# NMEA-v8_3-iso.net
KiCad netlist of a schematic drawn in EAGLE
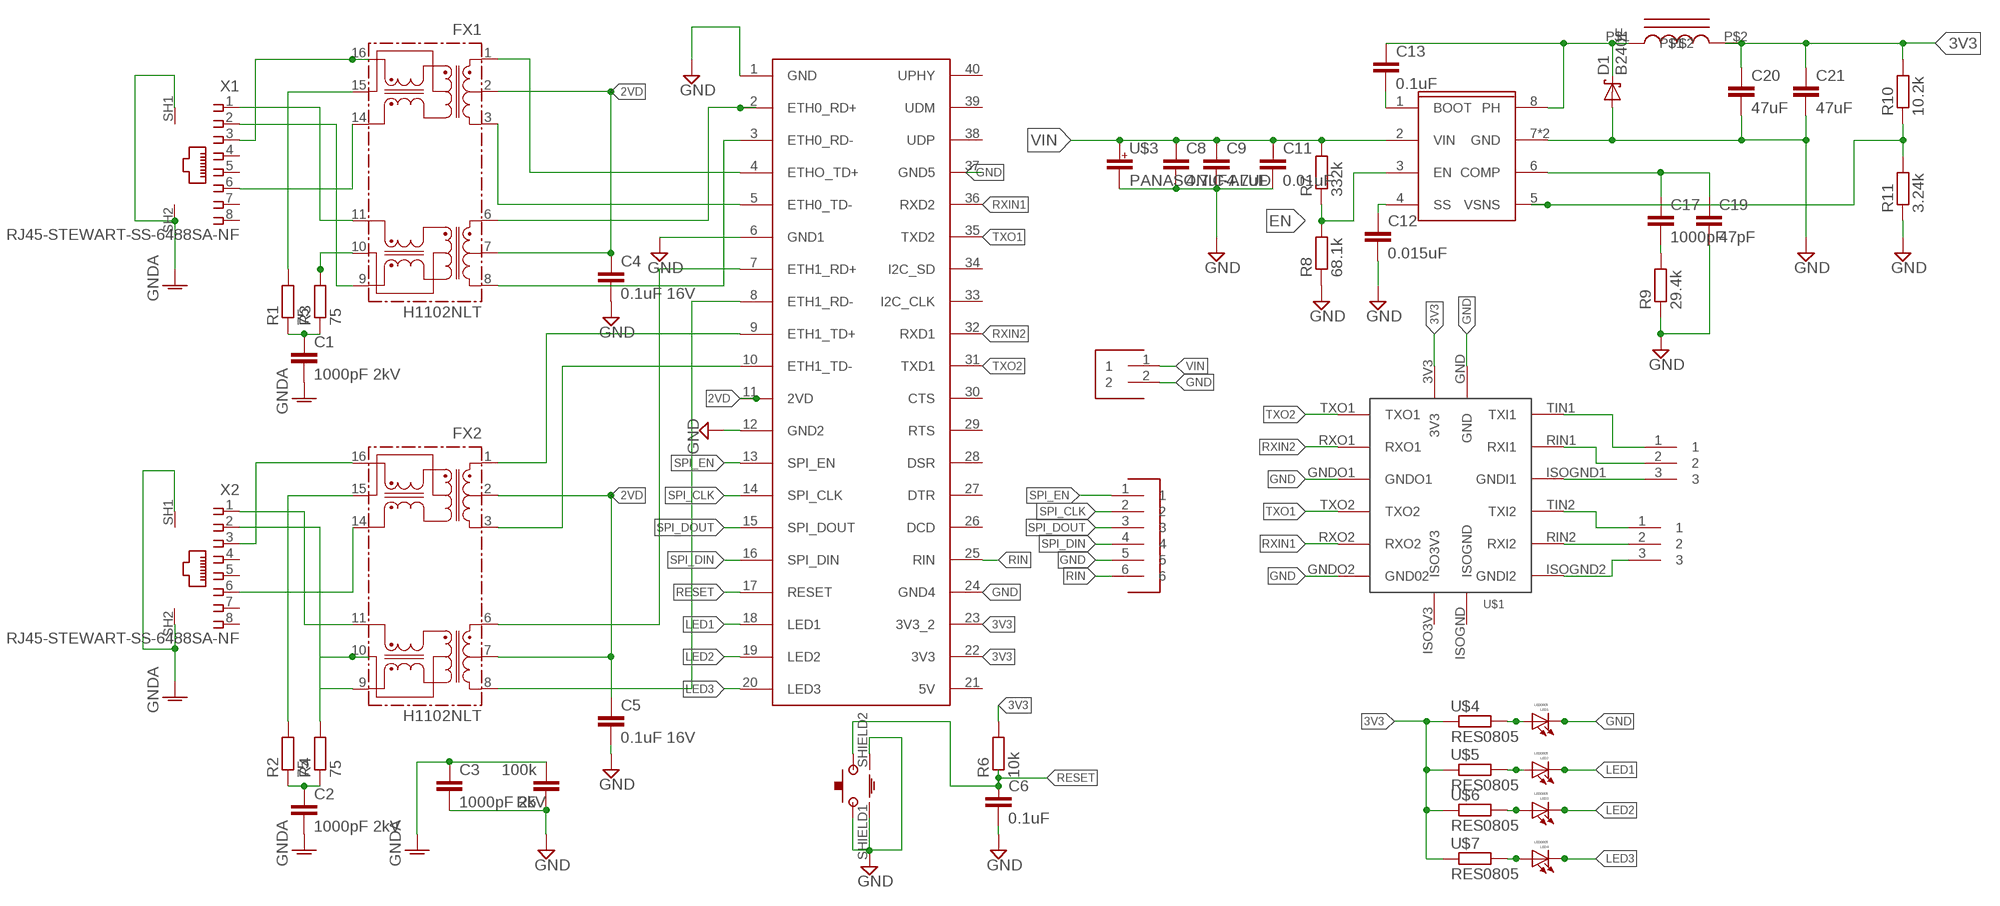
[diagram p0: schematic, sheet 1]

(export (version "E")
  (design (tool "Eeschema 10.0.6"))
  (components
    (comp (ref "C1")
      (value "1000pF 2kV")
      (footprint "eagle-import:1206")
      (libsource (lib "eagle-import") (part "CAP1206"))
    )
    (comp (ref "C2")
      (value "1000pF 2kV")
      (footprint "eagle-import:1206")
      (libsource (lib "eagle-import") (part "CAP1206"))
    )
    (comp (ref "C3")
      (value "1000pF 2kV")
      (footprint "eagle-import:1206")
      (libsource (lib "eagle-import") (part "CAP1206"))
    )
    (comp (ref "C4")
      (value "0.1uF 16V")
      (footprint "eagle-import:0603")
      (libsource (lib "eagle-import") (part "CAP0603"))
    )
    (comp (ref "C5")
      (value "0.1uF 16V")
      (footprint "eagle-import:0603")
      (libsource (lib "eagle-import") (part "CAP0603"))
    )
    (comp (ref "C6")
      (value "0.1uF")
      (footprint "eagle-import:0603")
      (libsource (lib "eagle-import") (part "CAP0603"))
    )
    (comp (ref "C8")
      (value "4.7uF")
      (footprint "eagle-import:1210")
      (libsource (lib "eagle-import") (part "CAP1210"))
    )
    (comp (ref "C9")
      (value "4.7uF")
      (footprint "eagle-import:1210")
      (libsource (lib "eagle-import") (part "CAP1210"))
    )
    (comp (ref "C11")
      (value "0.01uF")
      (footprint "eagle-import:0603")
      (libsource (lib "eagle-import") (part "CAP0603"))
    )
    (comp (ref "C12")
      (value "0.015uF")
      (footprint "eagle-import:0603")
      (libsource (lib "eagle-import") (part "CAP0603"))
    )
    (comp (ref "C13")
      (value "0.1uF")
      (footprint "eagle-import:0603")
      (libsource (lib "eagle-import") (part "CAP0603"))
    )
    (comp (ref "C17")
      (value "1000pF")
      (footprint "eagle-import:0603")
      (libsource (lib "eagle-import") (part "CAP0603"))
    )
    (comp (ref "C19")
      (value "47pF")
      (footprint "eagle-import:0603")
      (libsource (lib "eagle-import") (part "CAP0603"))
    )
    (comp (ref "C20")
      (value "47uF")
      (footprint "eagle-import:1206")
      (libsource (lib "eagle-import") (part "CAP1206"))
    )
    (comp (ref "C21")
      (value "47uF")
      (footprint "eagle-import:1206")
      (libsource (lib "eagle-import") (part "CAP1206"))
    )
    (comp (ref "CARAMBOLA")
      (value "CARAMBOLACREAM")
      (footprint "eagle-import:CARAMBOLA-CREAM")
      (libsource (lib "eagle-import") (part "CARAMBOLACREAM"))
    )
    (comp (ref "D1")
      (value "B240F")
      (footprint "eagle-import:SMB")
      (libsource (lib "eagle-import") (part "B240F"))
    )
    (comp (ref "DATA1")
      (value "CON-3CREAM")
      (footprint "eagle-import:CON-3-CREAM")
      (libsource (lib "eagle-import") (part "CON-3CREAM"))
    )
    (comp (ref "DATA2")
      (value "CON-3CREAM")
      (footprint "eagle-import:CON-3-CREAM")
      (libsource (lib "eagle-import") (part "CON-3CREAM"))
    )
    (comp (ref "FX1")
      (value "H1102NLT")
      (footprint "eagle-import:H_HX1XXXNL")
      (libsource (lib "eagle-import") (part "H1102NLT"))
    )
    (comp (ref "FX2")
      (value "H1102NLT")
      (footprint "eagle-import:H_HX1XXXNL")
      (libsource (lib "eagle-import") (part "H1102NLT"))
    )
    (comp (ref "J1")
      (value "CON-5MM-2")
      (footprint "eagle-import:CON--5MM-2")
      (libsource (lib "eagle-import") (part "CON-5MM-2"))
    )
    (comp (ref "L1")
      (value "CLF_TDK_INDUCTORCLF10040")
      (footprint "eagle-import:CLF10040")
      (libsource (lib "eagle-import") (part "CLF_TDK_INDUCTORCLF10040"))
    )
    (comp (ref "LED1")
      (value "LED0805")
      (footprint "eagle-import:L0805")
      (libsource (lib "eagle-import") (part "LED0805"))
    )
    (comp (ref "LED2")
      (value "LED0805")
      (footprint "eagle-import:L0805")
      (libsource (lib "eagle-import") (part "LED0805"))
    )
    (comp (ref "LED3")
      (value "LED0805")
      (footprint "eagle-import:L0805")
      (libsource (lib "eagle-import") (part "LED0805"))
    )
    (comp (ref "LED4")
      (value "LED0805")
      (footprint "eagle-import:L0805")
      (libsource (lib "eagle-import") (part "LED0805"))
    )
    (comp (ref "R1")
      (value "75")
      (footprint "eagle-import:0603")
      (libsource (lib "eagle-import") (part "RES0603"))
    )
    (comp (ref "R2")
      (value "75")
      (footprint "eagle-import:0603")
      (libsource (lib "eagle-import") (part "RES0603"))
    )
    (comp (ref "R3")
      (value "75")
      (footprint "eagle-import:0603")
      (libsource (lib "eagle-import") (part "RES0603"))
    )
    (comp (ref "R4")
      (value "75")
      (footprint "eagle-import:0603")
      (libsource (lib "eagle-import") (part "RES0603"))
    )
    (comp (ref "R5")
      (value "100k")
      (footprint "eagle-import:1206")
      (libsource (lib "eagle-import") (part "CAP1206"))
    )
    (comp (ref "R6")
      (value "10k")
      (footprint "eagle-import:0603")
      (libsource (lib "eagle-import") (part "RES0603"))
    )
    (comp (ref "R7")
      (value "332k")
      (footprint "eagle-import:0603")
      (libsource (lib "eagle-import") (part "RES0603"))
    )
    (comp (ref "R8")
      (value "68.1k")
      (footprint "eagle-import:0603")
      (libsource (lib "eagle-import") (part "RES0603"))
    )
    (comp (ref "R9")
      (value "29.4k")
      (footprint "eagle-import:0603")
      (libsource (lib "eagle-import") (part "RES0603"))
    )
    (comp (ref "R10")
      (value "10.2k")
      (footprint "eagle-import:0603")
      (libsource (lib "eagle-import") (part "RES0603"))
    )
    (comp (ref "R11")
      (value "3.24k")
      (footprint "eagle-import:0603")
      (libsource (lib "eagle-import") (part "RES0603"))
    )
    (comp (ref "U$1")
      (value "ISO-BOARDV1")
      (footprint "eagle-import:ISO-BOARD")
      (libsource (lib "eagle-import") (part "ISO-BOARDV1"))
    )
    (comp (ref "U$2")
      (value "TACTILE-SWITCH-FSMRA1J")
      (footprint "eagle-import:TACTILE-SWITCH-FSMRA1J")
      (libsource (lib "eagle-import") (part "TACTILE-SWITCH-FSMRA1J"))
    )
    (comp (ref "U$3")
      (value "PANASONIC-ALUD")
      (footprint "eagle-import:PANASONIC_D")
      (libsource (lib "eagle-import") (part "PANASONIC-ALUD"))
    )
    (comp (ref "U$4")
      (value "RES0805")
      (footprint "eagle-import:0603")
      (libsource (lib "eagle-import") (part "RES0603"))
    )
    (comp (ref "U$5")
      (value "RES0805")
      (footprint "eagle-import:0603")
      (libsource (lib "eagle-import") (part "RES0603"))
    )
    (comp (ref "U$6")
      (value "RES0805")
      (footprint "eagle-import:0603")
      (libsource (lib "eagle-import") (part "RES0603"))
    )
    (comp (ref "U$7")
      (value "RES0805")
      (footprint "eagle-import:0603")
      (libsource (lib "eagle-import") (part "RES0603"))
    )
    (comp (ref "U$8")
      (value "CON-6")
      (footprint "eagle-import:CON-6")
      (libsource (lib "eagle-import") (part "CON-6"))
    )
    (comp (ref "U8")
      (value "TPS54231")
      (footprint "eagle-import:SOIC-THERMAL")
      (libsource (lib "eagle-import") (part "TPS54231"))
    )
    (comp (ref "X1")
      (value "RJ45-STEWART-SS-6488SA-NF")
      (footprint "eagle-import:RJ45-STEWART-6488")
      (libsource (lib "eagle-import") (part "RJ45-STEWART-SS-6488SA-NF"))
    )
    (comp (ref "X2")
      (value "RJ45-STEWART-SS-6488SA-NF")
      (footprint "eagle-import:RJ45-STEWART-6488")
      (libsource (lib "eagle-import") (part "RJ45-STEWART-SS-6488SA-NF"))
    )
  )
  (nets
    (net (code "1") (name "2VD") (class "Default")
      (node (ref "C4") (pin "1") (pinfunction "1_1") (pintype "passive"))
      (node (ref "C5") (pin "1") (pinfunction "1_1") (pintype "passive"))
      (node (ref "CARAMBOLA") (pin "11") (pinfunction "2VD_11") (pintype "bidirectional"))
      (node (ref "FX1") (pin "2") (pinfunction "2_2") (pintype "passive"))
      (node (ref "FX1") (pin "7") (pinfunction "7_7") (pintype "passive"))
      (node (ref "FX2") (pin "2") (pinfunction "2_2") (pintype "passive"))
      (node (ref "FX2") (pin "7") (pinfunction "7_7") (pintype "passive"))
    )
    (net (code "2") (name "3V3") (class "Default")
      (node (ref "C20") (pin "1") (pinfunction "1_1") (pintype "passive"))
      (node (ref "C21") (pin "1") (pinfunction "1_1") (pintype "passive"))
      (node (ref "CARAMBOLA") (pin "22") (pinfunction "3V3_22") (pintype "bidirectional"))
      (node (ref "CARAMBOLA") (pin "23") (pinfunction "3V3_2_23") (pintype "bidirectional"))
      (node (ref "L1") (pin "P$2") (pinfunction "P$2_P$2") (pintype "bidirectional"))
      (node (ref "R10") (pin "2") (pinfunction "2_2") (pintype "passive"))
      (node (ref "R6") (pin "2") (pinfunction "2_2") (pintype "passive"))
      (node (ref "U$1") (pin "3V3") (pinfunction "3V3_3V3") (pintype "bidirectional"))
      (node (ref "U$4") (pin "1") (pinfunction "1_1") (pintype "passive"))
      (node (ref "U$5") (pin "1") (pinfunction "1_1") (pintype "passive"))
      (node (ref "U$6") (pin "1") (pinfunction "1_1") (pintype "passive"))
      (node (ref "U$7") (pin "1") (pinfunction "1_1") (pintype "passive"))
    )
    (net (code "3") (name "EN") (class "Default")
      (node (ref "R7") (pin "1") (pinfunction "1_1") (pintype "passive"))
      (node (ref "R8") (pin "2") (pinfunction "2_2") (pintype "passive"))
      (node (ref "U8") (pin "3") (pinfunction "EN_3") (pintype "bidirectional"))
    )
    (net (code "4") (name "GND") (class "Default")
      (node (ref "C11") (pin "2") (pinfunction "2_2") (pintype "passive"))
      (node (ref "C12") (pin "2") (pinfunction "2_2") (pintype "passive"))
      (node (ref "C19") (pin "2") (pinfunction "2_2") (pintype "passive"))
      (node (ref "C20") (pin "2") (pinfunction "2_2") (pintype "passive"))
      (node (ref "C21") (pin "2") (pinfunction "2_2") (pintype "passive"))
      (node (ref "C3") (pin "2") (pinfunction "2_2") (pintype "passive"))
      (node (ref "C4") (pin "2") (pinfunction "2_2") (pintype "passive"))
      (node (ref "C5") (pin "2") (pinfunction "2_2") (pintype "passive"))
      (node (ref "C6") (pin "2") (pinfunction "2_2") (pintype "passive"))
      (node (ref "C8") (pin "2") (pinfunction "2_2") (pintype "passive"))
      (node (ref "C9") (pin "2") (pinfunction "2_2") (pintype "passive"))
      (node (ref "CARAMBOLA") (pin "1") (pinfunction "GND_1") (pintype "bidirectional"))
      (node (ref "CARAMBOLA") (pin "12") (pinfunction "GND2_12") (pintype "bidirectional"))
      (node (ref "CARAMBOLA") (pin "24") (pinfunction "GND4_24") (pintype "bidirectional"))
      (node (ref "CARAMBOLA") (pin "37") (pinfunction "GND5_37") (pintype "bidirectional"))
      (node (ref "CARAMBOLA") (pin "6") (pinfunction "GND1_6") (pintype "bidirectional"))
      (node (ref "D1") (pin "A") (pinfunction "A_A") (pintype "passive"))
      (node (ref "J1") (pin "2") (pinfunction "2_2") (pintype "bidirectional"))
      (node (ref "LED1") (pin "C") (pinfunction "C_C") (pintype "passive"))
      (node (ref "R11") (pin "1") (pinfunction "1_1") (pintype "passive"))
      (node (ref "R5") (pin "1") (pinfunction "1_1") (pintype "passive"))
      (node (ref "R8") (pin "1") (pinfunction "1_1") (pintype "passive"))
      (node (ref "R9") (pin "1") (pinfunction "1_1") (pintype "passive"))
      (node (ref "U$1") (pin "GND") (pinfunction "GND_GND") (pintype "bidirectional"))
      (node (ref "U$1") (pin "GNDO1") (pinfunction "GNDO1_GNDO1") (pintype "bidirectional"))
      (node (ref "U$1") (pin "GNDO2") (pinfunction "GND02_GNDO2") (pintype "bidirectional"))
      (node (ref "U$2") (pin "2") (pinfunction "2_2") (pintype "bidirectional"))
      (node (ref "U$2") (pin "SHIELD1") (pinfunction "SHIELD1_SHIELD1") (pintype "bidirectional"))
      (node (ref "U$2") (pin "SHIELD2") (pinfunction "SHIELD2_SHIELD2") (pintype "bidirectional"))
      (node (ref "U$3") (pin "-") (pinfunction "-_-") (pintype "passive"))
      (node (ref "U$8") (pin "5") (pinfunction "5_5") (pintype "bidirectional"))
      (node (ref "U8") (pin "7") (pinfunction "GND_7") (pintype "bidirectional"))
      (node (ref "U8") (pin "P$1") (pinfunction "GND_P$1") (pintype "bidirectional"))
    )
    (net (code "5") (name "GNDA") (class "Default")
      (node (ref "C1") (pin "2") (pinfunction "2_2") (pintype "passive"))
      (node (ref "C2") (pin "2") (pinfunction "2_2") (pintype "passive"))
      (node (ref "C3") (pin "1") (pinfunction "1_1") (pintype "passive"))
      (node (ref "R5") (pin "2") (pinfunction "2_2") (pintype "passive"))
      (node (ref "X1") (pin "SH1") (pinfunction "SH1_SH1") (pintype "bidirectional"))
      (node (ref "X1") (pin "SH2") (pinfunction "SH2_SH2") (pintype "bidirectional"))
      (node (ref "X2") (pin "SH1") (pinfunction "SH1_SH1") (pintype "bidirectional"))
      (node (ref "X2") (pin "SH2") (pinfunction "SH2_SH2") (pintype "bidirectional"))
    )
    (net (code "6") (name "LED1") (class "Default")
      (node (ref "CARAMBOLA") (pin "18") (pinfunction "LED1_18") (pintype "bidirectional"))
      (node (ref "LED2") (pin "C") (pinfunction "C_C") (pintype "passive"))
    )
    (net (code "7") (name "LED2") (class "Default")
      (node (ref "CARAMBOLA") (pin "19") (pinfunction "LED2_19") (pintype "bidirectional"))
      (node (ref "LED3") (pin "C") (pinfunction "C_C") (pintype "passive"))
    )
    (net (code "8") (name "LED3") (class "Default")
      (node (ref "CARAMBOLA") (pin "20") (pinfunction "LED3_20") (pintype "bidirectional"))
      (node (ref "LED4") (pin "C") (pinfunction "C_C") (pintype "passive"))
    )
    (net (code "9") (name "Net-(C1-Pad1)") (class "Default")
      (node (ref "C1") (pin "1") (pinfunction "1_1") (pintype "passive"))
      (node (ref "R1") (pin "1") (pinfunction "1_1") (pintype "passive"))
      (node (ref "R3") (pin "1") (pinfunction "1_1") (pintype "passive"))
    )
    (net (code "10") (name "Net-(C2-Pad1)") (class "Default")
      (node (ref "C2") (pin "1") (pinfunction "1_1") (pintype "passive"))
      (node (ref "R2") (pin "1") (pinfunction "1_1") (pintype "passive"))
      (node (ref "R4") (pin "1") (pinfunction "1_1") (pintype "passive"))
    )
    (net (code "11") (name "Net-(C17-Pad2)") (class "Default")
      (node (ref "C17") (pin "2") (pinfunction "2_2") (pintype "passive"))
      (node (ref "R9") (pin "2") (pinfunction "2_2") (pintype "passive"))
    )
    (net (code "12") (name "Net-(CARAMBOLA-ETH0_RD+)") (class "Default")
      (node (ref "CARAMBOLA") (pin "2") (pinfunction "ETH0_RD+_2") (pintype "bidirectional"))
      (node (ref "FX1") (pin "6") (pinfunction "6_6") (pintype "passive"))
    )
    (net (code "13") (name "Net-(CARAMBOLA-ETH0_RD-)") (class "Default")
      (node (ref "CARAMBOLA") (pin "3") (pinfunction "ETH0_RD-_3") (pintype "bidirectional"))
      (node (ref "FX1") (pin "8") (pinfunction "8_8") (pintype "passive"))
    )
    (net (code "14") (name "Net-(CARAMBOLA-ETH0_TD-)") (class "Default")
      (node (ref "CARAMBOLA") (pin "5") (pinfunction "ETH0_TD-_5") (pintype "bidirectional"))
      (node (ref "FX1") (pin "3") (pinfunction "3_3") (pintype "passive"))
    )
    (net (code "15") (name "Net-(CARAMBOLA-ETH1_RD+)") (class "Default")
      (node (ref "CARAMBOLA") (pin "7") (pinfunction "ETH1_RD+_7") (pintype "bidirectional"))
      (node (ref "FX2") (pin "6") (pinfunction "6_6") (pintype "passive"))
    )
    (net (code "16") (name "Net-(CARAMBOLA-ETH1_RD-)") (class "Default")
      (node (ref "CARAMBOLA") (pin "8") (pinfunction "ETH1_RD-_8") (pintype "bidirectional"))
      (node (ref "FX2") (pin "8") (pinfunction "8_8") (pintype "passive"))
    )
    (net (code "17") (name "Net-(CARAMBOLA-ETH1_TD+)") (class "Default")
      (node (ref "CARAMBOLA") (pin "9") (pinfunction "ETH1_TD+_9") (pintype "bidirectional"))
      (node (ref "FX2") (pin "1") (pinfunction "1_1") (pintype "passive"))
    )
    (net (code "18") (name "Net-(CARAMBOLA-ETH1_TD-)") (class "Default")
      (node (ref "CARAMBOLA") (pin "10") (pinfunction "ETH1_TD-_10") (pintype "bidirectional"))
      (node (ref "FX2") (pin "3") (pinfunction "3_3") (pintype "passive"))
    )
    (net (code "19") (name "Net-(CARAMBOLA-ETHO_TD+)") (class "Default")
      (node (ref "CARAMBOLA") (pin "4") (pinfunction "ETHO_TD+_4") (pintype "bidirectional"))
      (node (ref "FX1") (pin "1") (pinfunction "1_1") (pintype "passive"))
    )
    (net (code "20") (name "Net-(FX1-Pad9)") (class "Default")
      (node (ref "FX1") (pin "9") (pinfunction "9_9") (pintype "passive"))
      (node (ref "X1") (pin "2") (pinfunction "2_2") (pintype "passive"))
    )
    (net (code "21") (name "Net-(FX1-Pad10)") (class "Default")
      (node (ref "FX1") (pin "10") (pinfunction "10_10") (pintype "passive"))
      (node (ref "R3") (pin "2") (pinfunction "2_2") (pintype "passive"))
    )
    (net (code "22") (name "Net-(FX1-Pad11)") (class "Default")
      (node (ref "FX1") (pin "11") (pinfunction "11_11") (pintype "passive"))
      (node (ref "X1") (pin "1") (pinfunction "1_1") (pintype "passive"))
    )
    (net (code "23") (name "Net-(FX1-Pad14)") (class "Default")
      (node (ref "FX1") (pin "14") (pinfunction "14_14") (pintype "passive"))
      (node (ref "X1") (pin "6") (pinfunction "6_6") (pintype "passive"))
    )
    (net (code "24") (name "Net-(FX1-Pad15)") (class "Default")
      (node (ref "FX1") (pin "15") (pinfunction "15_15") (pintype "passive"))
      (node (ref "R1") (pin "2") (pinfunction "2_2") (pintype "passive"))
    )
    (net (code "25") (name "Net-(FX1-Pad16)") (class "Default")
      (node (ref "FX1") (pin "16") (pinfunction "16_16") (pintype "passive"))
      (node (ref "X1") (pin "3") (pinfunction "3_3") (pintype "passive"))
    )
    (net (code "26") (name "Net-(FX2-Pad9)") (class "Default")
      (node (ref "FX2") (pin "9") (pinfunction "9_9") (pintype "passive"))
      (node (ref "X2") (pin "2") (pinfunction "2_2") (pintype "passive"))
    )
    (net (code "27") (name "Net-(FX2-Pad10)") (class "Default")
      (node (ref "FX2") (pin "10") (pinfunction "10_10") (pintype "passive"))
      (node (ref "R4") (pin "2") (pinfunction "2_2") (pintype "passive"))
    )
    (net (code "28") (name "Net-(FX2-Pad11)") (class "Default")
      (node (ref "FX2") (pin "11") (pinfunction "11_11") (pintype "passive"))
      (node (ref "X2") (pin "1") (pinfunction "1_1") (pintype "passive"))
    )
    (net (code "29") (name "Net-(FX2-Pad14)") (class "Default")
      (node (ref "FX2") (pin "14") (pinfunction "14_14") (pintype "passive"))
      (node (ref "X2") (pin "6") (pinfunction "6_6") (pintype "passive"))
    )
    (net (code "30") (name "Net-(FX2-Pad15)") (class "Default")
      (node (ref "FX2") (pin "15") (pinfunction "15_15") (pintype "passive"))
      (node (ref "R2") (pin "2") (pinfunction "2_2") (pintype "passive"))
    )
    (net (code "31") (name "Net-(FX2-Pad16)") (class "Default")
      (node (ref "FX2") (pin "16") (pinfunction "16_16") (pintype "passive"))
      (node (ref "X2") (pin "3") (pinfunction "3_3") (pintype "passive"))
    )
    (net (code "32") (name "Net-(LED1-PadA)") (class "Default")
      (node (ref "LED1") (pin "A") (pinfunction "A_A") (pintype "passive"))
      (node (ref "U$4") (pin "2") (pinfunction "2_2") (pintype "passive"))
    )
    (net (code "33") (name "Net-(LED2-PadA)") (class "Default")
      (node (ref "LED2") (pin "A") (pinfunction "A_A") (pintype "passive"))
      (node (ref "U$5") (pin "2") (pinfunction "2_2") (pintype "passive"))
    )
    (net (code "34") (name "Net-(LED3-PadA)") (class "Default")
      (node (ref "LED3") (pin "A") (pinfunction "A_A") (pintype "passive"))
      (node (ref "U$6") (pin "2") (pinfunction "2_2") (pintype "passive"))
    )
    (net (code "35") (name "Net-(LED4-PadA)") (class "Default")
      (node (ref "LED4") (pin "A") (pinfunction "A_A") (pintype "passive"))
      (node (ref "U$7") (pin "2") (pinfunction "2_2") (pintype "passive"))
    )
    (net (code "36") (name "Net-(U$1-GNDI1)") (class "Default")
      (node (ref "DATA1") (pin "3") (pinfunction "3_3") (pintype "bidirectional"))
      (node (ref "U$1") (pin "ISOGND1") (pinfunction "GNDI1_ISOGND1") (pintype "bidirectional"))
    )
    (net (code "37") (name "Net-(U$1-GNDI2)") (class "Default")
      (node (ref "DATA2") (pin "3") (pinfunction "3_3") (pintype "bidirectional"))
      (node (ref "U$1") (pin "ISOGND2") (pinfunction "GNDI2_ISOGND2") (pintype "bidirectional"))
    )
    (net (code "38") (name "Net-(U$1-RXI1)") (class "Default")
      (node (ref "DATA1") (pin "2") (pinfunction "2_2") (pintype "bidirectional"))
      (node (ref "U$1") (pin "RIN1") (pinfunction "RXI1_RIN1") (pintype "bidirectional"))
    )
    (net (code "39") (name "Net-(U$1-RXI2)") (class "Default")
      (node (ref "DATA2") (pin "2") (pinfunction "2_2") (pintype "bidirectional"))
      (node (ref "U$1") (pin "RIN2") (pinfunction "RXI2_RIN2") (pintype "bidirectional"))
    )
    (net (code "40") (name "Net-(U$1-TXI1)") (class "Default")
      (node (ref "DATA1") (pin "1") (pinfunction "1_1") (pintype "bidirectional"))
      (node (ref "U$1") (pin "TIN1") (pinfunction "TXI1_TIN1") (pintype "bidirectional"))
    )
    (net (code "41") (name "Net-(U$1-TXI2)") (class "Default")
      (node (ref "DATA2") (pin "1") (pinfunction "1_1") (pintype "bidirectional"))
      (node (ref "U$1") (pin "TIN2") (pinfunction "TXI2_TIN2") (pintype "bidirectional"))
    )
    (net (code "42") (name "Net-(U8-BOOT)") (class "Default")
      (node (ref "C13") (pin "2") (pinfunction "2_2") (pintype "passive"))
      (node (ref "U8") (pin "1") (pinfunction "BOOT_1") (pintype "bidirectional"))
    )
    (net (code "43") (name "Net-(U8-COMP)") (class "Default")
      (node (ref "C17") (pin "1") (pinfunction "1_1") (pintype "passive"))
      (node (ref "C19") (pin "1") (pinfunction "1_1") (pintype "passive"))
      (node (ref "U8") (pin "6") (pinfunction "COMP_6") (pintype "bidirectional"))
    )
    (net (code "44") (name "Net-(U8-PH)") (class "Default")
      (node (ref "C13") (pin "1") (pinfunction "1_1") (pintype "passive"))
      (node (ref "D1") (pin "C") (pinfunction "C_C") (pintype "passive"))
      (node (ref "L1") (pin "P$1") (pinfunction "P$1_P$1") (pintype "bidirectional"))
      (node (ref "U8") (pin "8") (pinfunction "PH_8") (pintype "bidirectional"))
    )
    (net (code "45") (name "Net-(U8-SS)") (class "Default")
      (node (ref "C12") (pin "1") (pinfunction "1_1") (pintype "passive"))
      (node (ref "U8") (pin "4") (pinfunction "SS_4") (pintype "bidirectional"))
    )
    (net (code "46") (name "Net-(U8-VSNS)") (class "Default")
      (node (ref "R10") (pin "1") (pinfunction "1_1") (pintype "passive"))
      (node (ref "R11") (pin "2") (pinfunction "2_2") (pintype "passive"))
      (node (ref "U8") (pin "5") (pinfunction "VSNS_5") (pintype "bidirectional"))
    )
    (net (code "47") (name "RESET") (class "Default")
      (node (ref "C6") (pin "1") (pinfunction "1_1") (pintype "passive"))
      (node (ref "CARAMBOLA") (pin "17") (pinfunction "RESET_17") (pintype "bidirectional"))
      (node (ref "R6") (pin "1") (pinfunction "1_1") (pintype "passive"))
      (node (ref "U$2") (pin "1") (pinfunction "1_1") (pintype "bidirectional"))
    )
    (net (code "48") (name "RIN") (class "Default")
      (node (ref "CARAMBOLA") (pin "25") (pinfunction "RIN_25") (pintype "bidirectional"))
      (node (ref "U$8") (pin "6") (pinfunction "6_6") (pintype "bidirectional"))
    )
    (net (code "49") (name "RXIN1") (class "Default")
      (node (ref "CARAMBOLA") (pin "36") (pinfunction "RXD2_36") (pintype "bidirectional"))
      (node (ref "U$1") (pin "RXO2") (pinfunction "RXO2_RXO2") (pintype "bidirectional"))
    )
    (net (code "50") (name "RXIN2") (class "Default")
      (node (ref "CARAMBOLA") (pin "32") (pinfunction "RXD1_32") (pintype "bidirectional"))
      (node (ref "U$1") (pin "RXO1") (pinfunction "RXO1_RXO1") (pintype "bidirectional"))
    )
    (net (code "51") (name "SPI_CLK") (class "Default")
      (node (ref "CARAMBOLA") (pin "14") (pinfunction "SPI_CLK_14") (pintype "bidirectional"))
      (node (ref "U$8") (pin "2") (pinfunction "2_2") (pintype "bidirectional"))
    )
    (net (code "52") (name "SPI_DIN") (class "Default")
      (node (ref "CARAMBOLA") (pin "16") (pinfunction "SPI_DIN_16") (pintype "bidirectional"))
      (node (ref "U$8") (pin "4") (pinfunction "4_4") (pintype "bidirectional"))
    )
    (net (code "53") (name "SPI_DOUT") (class "Default")
      (node (ref "CARAMBOLA") (pin "15") (pinfunction "SPI_DOUT_15") (pintype "bidirectional"))
      (node (ref "U$8") (pin "3") (pinfunction "3_3") (pintype "bidirectional"))
    )
    (net (code "54") (name "SPI_EN") (class "Default")
      (node (ref "CARAMBOLA") (pin "13") (pinfunction "SPI_EN_13") (pintype "bidirectional"))
      (node (ref "U$8") (pin "1") (pinfunction "1_1") (pintype "bidirectional"))
    )
    (net (code "55") (name "TXO1") (class "Default")
      (node (ref "CARAMBOLA") (pin "35") (pinfunction "TXD2_35") (pintype "bidirectional"))
      (node (ref "U$1") (pin "TXO2") (pinfunction "TXO2_TXO2") (pintype "bidirectional"))
    )
    (net (code "56") (name "TXO2") (class "Default")
      (node (ref "CARAMBOLA") (pin "31") (pinfunction "TXD1_31") (pintype "bidirectional"))
      (node (ref "U$1") (pin "TXO1") (pinfunction "TXO1_TXO1") (pintype "bidirectional"))
    )
    (net (code "57") (name "VIN") (class "Default")
      (node (ref "C11") (pin "1") (pinfunction "1_1") (pintype "passive"))
      (node (ref "C8") (pin "1") (pinfunction "1_1") (pintype "passive"))
      (node (ref "C9") (pin "1") (pinfunction "1_1") (pintype "passive"))
      (node (ref "J1") (pin "1") (pinfunction "1_1") (pintype "bidirectional"))
      (node (ref "R7") (pin "2") (pinfunction "2_2") (pintype "passive"))
      (node (ref "U$3") (pin "+") (pinfunction "+_+") (pintype "passive"))
      (node (ref "U8") (pin "2") (pinfunction "VIN_2") (pintype "bidirectional"))
    )
    (net (code "58") (name "unconnected-(CARAMBOLA-5V-Pad21)") (class "Default")
      (node (ref "CARAMBOLA") (pin "21") (pinfunction "5V_21") (pintype "bidirectional"))
    )
    (net (code "59") (name "unconnected-(CARAMBOLA-CTS-Pad30)") (class "Default")
      (node (ref "CARAMBOLA") (pin "30") (pinfunction "CTS_30") (pintype "bidirectional"))
    )
    (net (code "60") (name "unconnected-(CARAMBOLA-DCD-Pad26)") (class "Default")
      (node (ref "CARAMBOLA") (pin "26") (pinfunction "DCD_26") (pintype "bidirectional"))
    )
    (net (code "61") (name "unconnected-(CARAMBOLA-DSR-Pad28)") (class "Default")
      (node (ref "CARAMBOLA") (pin "28") (pinfunction "DSR_28") (pintype "bidirectional"))
    )
    (net (code "62") (name "unconnected-(CARAMBOLA-DTR-Pad27)") (class "Default")
      (node (ref "CARAMBOLA") (pin "27") (pinfunction "DTR_27") (pintype "bidirectional"))
    )
    (net (code "63") (name "unconnected-(CARAMBOLA-I2C_CLK-Pad33)") (class "Default")
      (node (ref "CARAMBOLA") (pin "33") (pinfunction "I2C_CLK_33") (pintype "bidirectional"))
    )
    (net (code "64") (name "unconnected-(CARAMBOLA-I2C_SD-Pad34)") (class "Default")
      (node (ref "CARAMBOLA") (pin "34") (pinfunction "I2C_SD_34") (pintype "bidirectional"))
    )
    (net (code "65") (name "unconnected-(CARAMBOLA-RTS-Pad29)") (class "Default")
      (node (ref "CARAMBOLA") (pin "29") (pinfunction "RTS_29") (pintype "bidirectional"))
    )
    (net (code "66") (name "unconnected-(CARAMBOLA-UDM-Pad39)") (class "Default")
      (node (ref "CARAMBOLA") (pin "39") (pinfunction "UDM_39") (pintype "bidirectional"))
    )
    (net (code "67") (name "unconnected-(CARAMBOLA-UDP-Pad38)") (class "Default")
      (node (ref "CARAMBOLA") (pin "38") (pinfunction "UDP_38") (pintype "bidirectional"))
    )
    (net (code "68") (name "unconnected-(CARAMBOLA-UPHY-Pad40)") (class "Default")
      (node (ref "CARAMBOLA") (pin "40") (pinfunction "UPHY_40") (pintype "bidirectional"))
    )
    (net (code "69") (name "unconnected-(U$1-PadISO3V3)") (class "Default")
      (node (ref "U$1") (pin "ISO3V3") (pinfunction "ISO3V3_ISO3V3") (pintype "bidirectional"))
    )
    (net (code "70") (name "unconnected-(U$1-PadISOGND)") (class "Default")
      (node (ref "U$1") (pin "ISOGND") (pinfunction "ISOGND_ISOGND") (pintype "bidirectional"))
    )
    (net (code "71") (name "unconnected-(X1-Pad4)") (class "Default")
      (node (ref "X1") (pin "4") (pinfunction "4_4") (pintype "passive"))
    )
    (net (code "72") (name "unconnected-(X1-Pad5)") (class "Default")
      (node (ref "X1") (pin "5") (pinfunction "5_5") (pintype "passive"))
    )
    (net (code "73") (name "unconnected-(X1-Pad7)") (class "Default")
      (node (ref "X1") (pin "7") (pinfunction "7_7") (pintype "passive"))
    )
    (net (code "74") (name "unconnected-(X1-Pad8)") (class "Default")
      (node (ref "X1") (pin "8") (pinfunction "8_8") (pintype "passive"))
    )
    (net (code "75") (name "unconnected-(X2-Pad4)") (class "Default")
      (node (ref "X2") (pin "4") (pinfunction "4_4") (pintype "passive"))
    )
    (net (code "76") (name "unconnected-(X2-Pad5)") (class "Default")
      (node (ref "X2") (pin "5") (pinfunction "5_5") (pintype "passive"))
    )
    (net (code "77") (name "unconnected-(X2-Pad7)") (class "Default")
      (node (ref "X2") (pin "7") (pinfunction "7_7") (pintype "passive"))
    )
    (net (code "78") (name "unconnected-(X2-Pad8)") (class "Default")
      (node (ref "X2") (pin "8") (pinfunction "8_8") (pintype "passive"))
    )
  )
)
